# piston_stm.net
KiCad netlist of a schematic drawn in EAGLE
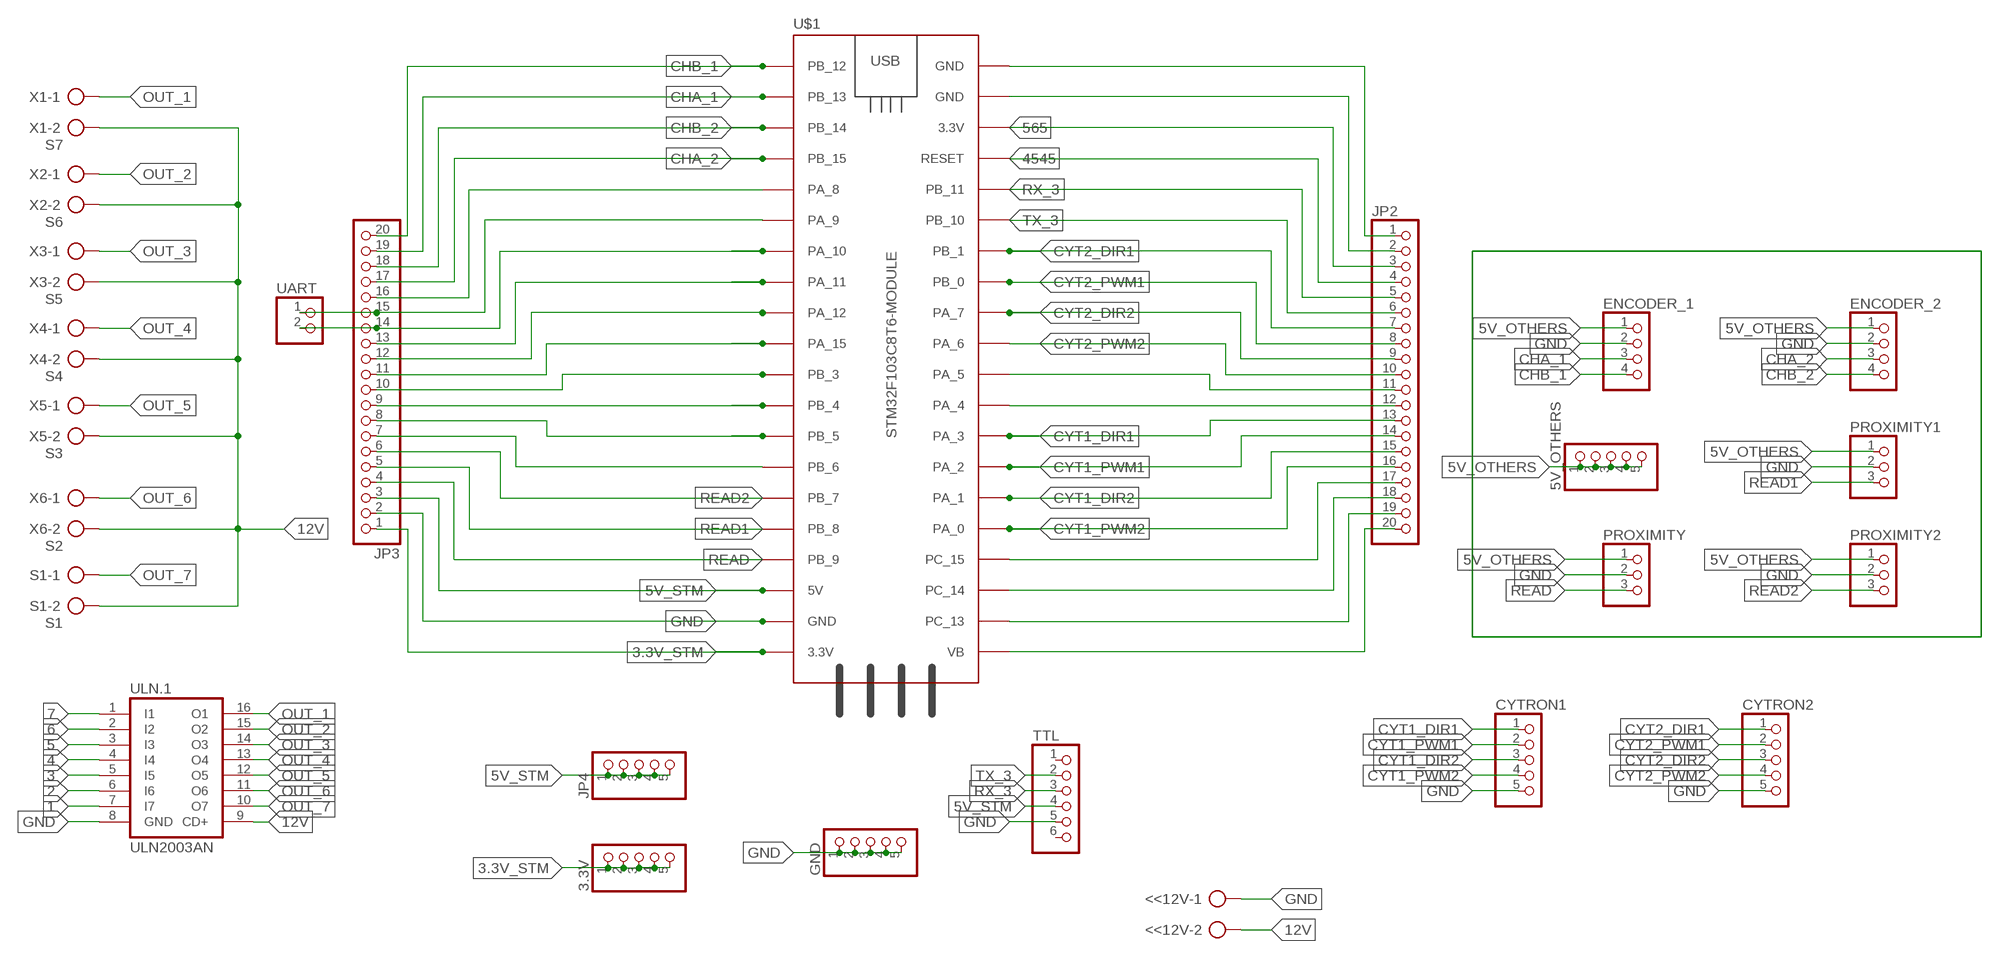
[diagram p0: schematic, sheet 1]

(export (version "E")
  (design (tool "Eeschema 10.0.6"))
  (components
    (comp (ref "3.3V")
      (value "PINHD-1X5")
      (footprint "eagle-import:1X05")
      (libsource (lib "eagle-import") (part "PINHD-1X5"))
    )
    (comp (ref "5V_OTHERS")
      (value "PINHD-1X5")
      (footprint "eagle-import:1X05")
      (libsource (lib "eagle-import") (part "PINHD-1X5"))
    )
    (comp (ref "<<12V")
      (value "AK300/2")
      (footprint "eagle-import:AK300_2")
      (libsource (lib "eagle-import") (part "AK300/2"))
    )
    (comp (ref "CYTRON1")
      (value "PINHD-5_DATA")
      (footprint "eagle-import:DATA_5")
      (libsource (lib "eagle-import") (part "PINHD-5_DATA"))
    )
    (comp (ref "CYTRON2")
      (value "PINHD-5_DATA")
      (footprint "eagle-import:DATA_5")
      (libsource (lib "eagle-import") (part "PINHD-5_DATA"))
    )
    (comp (ref "ENCODER_1")
      (value "PINHD-4_DATA")
      (footprint "eagle-import:DATA_4")
      (libsource (lib "eagle-import") (part "PINHD-4_DATA"))
    )
    (comp (ref "ENCODER_2")
      (value "PINHD-4_DATA")
      (footprint "eagle-import:DATA_4")
      (libsource (lib "eagle-import") (part "PINHD-4_DATA"))
    )
    (comp (ref "GND")
      (value "PINHD-1X5")
      (footprint "eagle-import:1X05")
      (libsource (lib "eagle-import") (part "PINHD-1X5"))
    )
    (comp (ref "JP2")
      (value "PINHD-1X20")
      (footprint "eagle-import:1X20")
      (libsource (lib "eagle-import") (part "PINHD-1X20"))
    )
    (comp (ref "JP3")
      (value "PINHD-1X20")
      (footprint "eagle-import:1X20")
      (libsource (lib "eagle-import") (part "PINHD-1X20"))
    )
    (comp (ref "JP4")
      (value "PINHD-1X5")
      (footprint "eagle-import:1X05")
      (libsource (lib "eagle-import") (part "PINHD-1X5"))
    )
    (comp (ref "PROXIMITY")
      (value "PINHD-3_DATA")
      (footprint "eagle-import:DATA_3")
      (libsource (lib "eagle-import") (part "PINHD-3_DATA"))
    )
    (comp (ref "PROXIMITY1")
      (value "PINHD-3_DATA")
      (footprint "eagle-import:DATA_3")
      (libsource (lib "eagle-import") (part "PINHD-3_DATA"))
    )
    (comp (ref "PROXIMITY2")
      (value "PINHD-3_DATA")
      (footprint "eagle-import:DATA_3")
      (libsource (lib "eagle-import") (part "PINHD-3_DATA"))
    )
    (comp (ref "S1")
      (value "S1")
      (footprint "eagle-import:AK300_2")
      (libsource (lib "eagle-import") (part "AK300/2"))
    )
    (comp (ref "TTL")
      (value "PINHD-6_DATA")
      (footprint "eagle-import:DATA_6")
      (libsource (lib "eagle-import") (part "PINHD-6_DATA"))
    )
    (comp (ref "U$1")
      (value "STM32F103C8T6-MODULE")
      (footprint "eagle-import:STM32F103C8T6-MODULE")
      (libsource (lib "eagle-import") (part "STM32F103C8T6-MODULE"))
    )
    (comp (ref "UART")
      (value "PINHD-2_DATA")
      (footprint "eagle-import:DATA_2")
      (libsource (lib "eagle-import") (part "PINHD-2_DATA"))
    )
    (comp (ref "ULN.1")
      (value "ULN2003AN")
      (footprint "eagle-import:DIL16")
      (libsource (lib "eagle-import") (part "ULN2003AN"))
    )
    (comp (ref "X1")
      (value "S7")
      (footprint "eagle-import:AK300_2")
      (libsource (lib "eagle-import") (part "AK300/2"))
    )
    (comp (ref "X2")
      (value "S6")
      (footprint "eagle-import:AK300_2")
      (libsource (lib "eagle-import") (part "AK300/2"))
    )
    (comp (ref "X3")
      (value "S5")
      (footprint "eagle-import:AK300_2")
      (libsource (lib "eagle-import") (part "AK300/2"))
    )
    (comp (ref "X4")
      (value "S4")
      (footprint "eagle-import:AK300_2")
      (libsource (lib "eagle-import") (part "AK300/2"))
    )
    (comp (ref "X5")
      (value "S3")
      (footprint "eagle-import:AK300_2")
      (libsource (lib "eagle-import") (part "AK300/2"))
    )
    (comp (ref "X6")
      (value "S2")
      (footprint "eagle-import:AK300_2")
      (libsource (lib "eagle-import") (part "AK300/2"))
    )
  )
  (nets
    (net (code "1") (name "1") (class "Default")
      (node (ref "JP3") (pin "13") (pinfunction "13_13") (pintype "passive"))
      (node (ref "U$1") (pin "PA_11") (pinfunction "PA_11_PA_11") (pintype "bidirectional"))
      (node (ref "ULN.1") (pin "7") (pinfunction "I7_7") (pintype "input"))
    )
    (net (code "2") (name "2") (class "Default")
      (node (ref "JP3") (pin "12") (pinfunction "12_12") (pintype "passive"))
      (node (ref "U$1") (pin "PA_12") (pinfunction "PA_12_PA_12") (pintype "bidirectional"))
      (node (ref "ULN.1") (pin "6") (pinfunction "I6_6") (pintype "input"))
    )
    (net (code "3") (name "3") (class "Default")
      (node (ref "JP3") (pin "11") (pinfunction "11_11") (pintype "passive"))
      (node (ref "U$1") (pin "PA_15") (pinfunction "PA_15_PA_15") (pintype "bidirectional"))
      (node (ref "ULN.1") (pin "5") (pinfunction "I5_5") (pintype "input"))
    )
    (net (code "4") (name "3.3V_STM") (class "Default")
      (node (ref "3.3V") (pin "1") (pinfunction "1_1") (pintype "passive"))
      (node (ref "3.3V") (pin "2") (pinfunction "2_2") (pintype "passive"))
      (node (ref "3.3V") (pin "3") (pinfunction "3_3") (pintype "passive"))
      (node (ref "3.3V") (pin "4") (pinfunction "4_4") (pintype "passive"))
      (node (ref "3.3V") (pin "5") (pinfunction "5_5") (pintype "passive"))
      (node (ref "JP3") (pin "1") (pinfunction "1_1") (pintype "passive"))
      (node (ref "U$1") (pin "3.3V_1") (pinfunction "3.3V_3.3V_1") (pintype "bidirectional"))
    )
    (net (code "5") (name "4") (class "Default")
      (node (ref "JP3") (pin "10") (pinfunction "10_10") (pintype "passive"))
      (node (ref "U$1") (pin "PB_3") (pinfunction "PB_3_PB_3") (pintype "bidirectional"))
      (node (ref "ULN.1") (pin "4") (pinfunction "I4_4") (pintype "input"))
    )
    (net (code "6") (name "5") (class "Default")
      (node (ref "JP3") (pin "9") (pinfunction "9_9") (pintype "passive"))
      (node (ref "U$1") (pin "PB_4") (pinfunction "PB_4_PB_4") (pintype "bidirectional"))
      (node (ref "ULN.1") (pin "3") (pinfunction "I3_3") (pintype "input"))
    )
    (net (code "7") (name "5V_OTHERS") (class "Default")
      (node (ref "5V_OTHERS") (pin "1") (pinfunction "1_1") (pintype "passive"))
      (node (ref "5V_OTHERS") (pin "2") (pinfunction "2_2") (pintype "passive"))
      (node (ref "5V_OTHERS") (pin "3") (pinfunction "3_3") (pintype "passive"))
      (node (ref "5V_OTHERS") (pin "4") (pinfunction "4_4") (pintype "passive"))
      (node (ref "5V_OTHERS") (pin "5") (pinfunction "5_5") (pintype "passive"))
      (node (ref "ENCODER_1") (pin "1") (pinfunction "1_1") (pintype "passive"))
      (node (ref "ENCODER_2") (pin "1") (pinfunction "1_1") (pintype "passive"))
      (node (ref "PROXIMITY") (pin "1") (pinfunction "1_1") (pintype "passive"))
      (node (ref "PROXIMITY1") (pin "1") (pinfunction "1_1") (pintype "passive"))
      (node (ref "PROXIMITY2") (pin "1") (pinfunction "1_1") (pintype "passive"))
    )
    (net (code "8") (name "5V_STM") (class "Default")
      (node (ref "JP3") (pin "3") (pinfunction "3_3") (pintype "passive"))
      (node (ref "JP4") (pin "1") (pinfunction "1_1") (pintype "passive"))
      (node (ref "JP4") (pin "2") (pinfunction "2_2") (pintype "passive"))
      (node (ref "JP4") (pin "3") (pinfunction "3_3") (pintype "passive"))
      (node (ref "JP4") (pin "4") (pinfunction "4_4") (pintype "passive"))
      (node (ref "JP4") (pin "5") (pinfunction "5_5") (pintype "passive"))
      (node (ref "TTL") (pin "4") (pinfunction "4_4") (pintype "passive"))
      (node (ref "U$1") (pin "5V") (pinfunction "5V_5V") (pintype "bidirectional"))
    )
    (net (code "9") (name "6") (class "Default")
      (node (ref "JP3") (pin "8") (pinfunction "8_8") (pintype "passive"))
      (node (ref "U$1") (pin "PB_5") (pinfunction "PB_5_PB_5") (pintype "bidirectional"))
      (node (ref "ULN.1") (pin "2") (pinfunction "I2_2") (pintype "input"))
    )
    (net (code "10") (name "7") (class "Default")
      (node (ref "JP2") (pin "12") (pinfunction "12_12") (pintype "passive"))
      (node (ref "U$1") (pin "PA_4") (pinfunction "PA_4_PA_4") (pintype "bidirectional"))
      (node (ref "ULN.1") (pin "1") (pinfunction "I1_1") (pintype "input"))
    )
    (net (code "11") (name "12V") (class "Default")
      (node (ref "<<12V") (pin "2") (pinfunction "KL_2") (pintype "passive"))
      (node (ref "S1") (pin "2") (pinfunction "KL_2") (pintype "passive"))
      (node (ref "ULN.1") (pin "9") (pinfunction "CD+_9") (pintype "passive"))
      (node (ref "X1") (pin "2") (pinfunction "KL_2") (pintype "passive"))
      (node (ref "X2") (pin "2") (pinfunction "KL_2") (pintype "passive"))
      (node (ref "X3") (pin "2") (pinfunction "KL_2") (pintype "passive"))
      (node (ref "X4") (pin "2") (pinfunction "KL_2") (pintype "passive"))
      (node (ref "X5") (pin "2") (pinfunction "KL_2") (pintype "passive"))
      (node (ref "X6") (pin "2") (pinfunction "KL_2") (pintype "passive"))
    )
    (net (code "12") (name "565") (class "Default")
      (node (ref "JP2") (pin "3") (pinfunction "3_3") (pintype "passive"))
      (node (ref "U$1") (pin "3.3V_2") (pinfunction "3.3V_3.3V_2") (pintype "bidirectional"))
    )
    (net (code "13") (name "4545") (class "Default")
      (node (ref "JP2") (pin "4") (pinfunction "4_4") (pintype "passive"))
      (node (ref "U$1") (pin "RESET") (pinfunction "RESET_RESET") (pintype "bidirectional"))
    )
    (net (code "14") (name "CHA_1") (class "Default")
      (node (ref "ENCODER_1") (pin "3") (pinfunction "3_3") (pintype "passive"))
      (node (ref "JP3") (pin "19") (pinfunction "19_19") (pintype "passive"))
      (node (ref "U$1") (pin "PB_13") (pinfunction "PB_13_PB_13") (pintype "bidirectional"))
    )
    (net (code "15") (name "CHA_2") (class "Default")
      (node (ref "ENCODER_2") (pin "3") (pinfunction "3_3") (pintype "passive"))
      (node (ref "JP3") (pin "17") (pinfunction "17_17") (pintype "passive"))
      (node (ref "U$1") (pin "PB_15") (pinfunction "PB_15_PB_15") (pintype "bidirectional"))
    )
    (net (code "16") (name "CHB_1") (class "Default")
      (node (ref "ENCODER_1") (pin "4") (pinfunction "4_4") (pintype "passive"))
      (node (ref "JP3") (pin "20") (pinfunction "20_20") (pintype "passive"))
      (node (ref "U$1") (pin "PB_12") (pinfunction "PB_12_PB_12") (pintype "bidirectional"))
    )
    (net (code "17") (name "CHB_2") (class "Default")
      (node (ref "ENCODER_2") (pin "4") (pinfunction "4_4") (pintype "passive"))
      (node (ref "JP3") (pin "18") (pinfunction "18_18") (pintype "passive"))
      (node (ref "U$1") (pin "PB_14") (pinfunction "PB_14_PB_14") (pintype "bidirectional"))
    )
    (net (code "18") (name "CYT1_DIR1") (class "Default")
      (node (ref "CYTRON1") (pin "1") (pinfunction "1_1") (pintype "passive"))
      (node (ref "JP2") (pin "13") (pinfunction "13_13") (pintype "passive"))
      (node (ref "U$1") (pin "PA_3") (pinfunction "PA_3_PA_3") (pintype "bidirectional"))
    )
    (net (code "19") (name "CYT1_DIR2") (class "Default")
      (node (ref "CYTRON1") (pin "3") (pinfunction "3_3") (pintype "passive"))
      (node (ref "JP2") (pin "15") (pinfunction "15_15") (pintype "passive"))
      (node (ref "U$1") (pin "PA_1") (pinfunction "PA_1_PA_1") (pintype "bidirectional"))
    )
    (net (code "20") (name "CYT1_PWM1") (class "Default")
      (node (ref "CYTRON1") (pin "2") (pinfunction "2_2") (pintype "passive"))
      (node (ref "JP2") (pin "14") (pinfunction "14_14") (pintype "passive"))
      (node (ref "U$1") (pin "PA_2") (pinfunction "PA_2_PA_2") (pintype "bidirectional"))
    )
    (net (code "21") (name "CYT1_PWM2") (class "Default")
      (node (ref "CYTRON1") (pin "4") (pinfunction "4_4") (pintype "passive"))
      (node (ref "JP2") (pin "16") (pinfunction "16_16") (pintype "passive"))
      (node (ref "U$1") (pin "PA_0") (pinfunction "PA_0_PA_0") (pintype "bidirectional"))
    )
    (net (code "22") (name "CYT2_DIR1") (class "Default")
      (node (ref "CYTRON2") (pin "1") (pinfunction "1_1") (pintype "passive"))
      (node (ref "JP2") (pin "7") (pinfunction "7_7") (pintype "passive"))
      (node (ref "U$1") (pin "PB_1") (pinfunction "PB_1_PB_1") (pintype "bidirectional"))
    )
    (net (code "23") (name "CYT2_DIR2") (class "Default")
      (node (ref "CYTRON2") (pin "3") (pinfunction "3_3") (pintype "passive"))
      (node (ref "JP2") (pin "9") (pinfunction "9_9") (pintype "passive"))
      (node (ref "U$1") (pin "PA_7") (pinfunction "PA_7_PA_7") (pintype "bidirectional"))
    )
    (net (code "24") (name "CYT2_PWM1") (class "Default")
      (node (ref "CYTRON2") (pin "2") (pinfunction "2_2") (pintype "passive"))
      (node (ref "JP2") (pin "8") (pinfunction "8_8") (pintype "passive"))
      (node (ref "U$1") (pin "PB_0") (pinfunction "PB_0_PB_0") (pintype "bidirectional"))
    )
    (net (code "25") (name "CYT2_PWM2") (class "Default")
      (node (ref "CYTRON2") (pin "4") (pinfunction "4_4") (pintype "passive"))
      (node (ref "JP2") (pin "10") (pinfunction "10_10") (pintype "passive"))
      (node (ref "U$1") (pin "PA_6") (pinfunction "PA_6_PA_6") (pintype "bidirectional"))
    )
    (net (code "26") (name "GND") (class "Default")
      (node (ref "<<12V") (pin "1") (pinfunction "KL_1") (pintype "passive"))
      (node (ref "CYTRON1") (pin "5") (pinfunction "5_5") (pintype "passive"))
      (node (ref "CYTRON2") (pin "5") (pinfunction "5_5") (pintype "passive"))
      (node (ref "ENCODER_1") (pin "2") (pinfunction "2_2") (pintype "passive"))
      (node (ref "ENCODER_2") (pin "2") (pinfunction "2_2") (pintype "passive"))
      (node (ref "GND") (pin "1") (pinfunction "1_1") (pintype "passive"))
      (node (ref "GND") (pin "2") (pinfunction "2_2") (pintype "passive"))
      (node (ref "GND") (pin "3") (pinfunction "3_3") (pintype "passive"))
      (node (ref "GND") (pin "4") (pinfunction "4_4") (pintype "passive"))
      (node (ref "GND") (pin "5") (pinfunction "5_5") (pintype "passive"))
      (node (ref "JP2") (pin "1") (pinfunction "1_1") (pintype "passive"))
      (node (ref "JP2") (pin "2") (pinfunction "2_2") (pintype "passive"))
      (node (ref "JP3") (pin "2") (pinfunction "2_2") (pintype "passive"))
      (node (ref "PROXIMITY") (pin "2") (pinfunction "2_2") (pintype "passive"))
      (node (ref "PROXIMITY1") (pin "2") (pinfunction "2_2") (pintype "passive"))
      (node (ref "PROXIMITY2") (pin "2") (pinfunction "2_2") (pintype "passive"))
      (node (ref "TTL") (pin "5") (pinfunction "5_5") (pintype "passive"))
      (node (ref "U$1") (pin "GND_1") (pinfunction "GND_GND_1") (pintype "bidirectional"))
      (node (ref "U$1") (pin "GND_2") (pinfunction "GND_GND_2") (pintype "bidirectional"))
      (node (ref "U$1") (pin "GND_3") (pinfunction "GND_GND_3") (pintype "power_in"))
      (node (ref "ULN.1") (pin "8") (pinfunction "GND_8") (pintype "power_in"))
    )
    (net (code "27") (name "Net-(JP2-Pad11)") (class "Default")
      (node (ref "JP2") (pin "11") (pinfunction "11_11") (pintype "passive"))
      (node (ref "U$1") (pin "PA_5") (pinfunction "PA_5_PA_5") (pintype "bidirectional"))
    )
    (net (code "28") (name "Net-(JP2-Pad17)") (class "Default")
      (node (ref "JP2") (pin "17") (pinfunction "17_17") (pintype "passive"))
      (node (ref "U$1") (pin "PC_15") (pinfunction "PC_15_PC_15") (pintype "bidirectional"))
    )
    (net (code "29") (name "Net-(JP2-Pad18)") (class "Default")
      (node (ref "JP2") (pin "18") (pinfunction "18_18") (pintype "passive"))
      (node (ref "U$1") (pin "PC_14") (pinfunction "PC_14_PC_14") (pintype "bidirectional"))
    )
    (net (code "30") (name "Net-(JP2-Pad19)") (class "Default")
      (node (ref "JP2") (pin "19") (pinfunction "19_19") (pintype "passive"))
      (node (ref "U$1") (pin "PC_13") (pinfunction "PC_13_PC_13") (pintype "bidirectional"))
    )
    (net (code "31") (name "Net-(JP2-Pad20)") (class "Default")
      (node (ref "JP2") (pin "20") (pinfunction "20_20") (pintype "passive"))
      (node (ref "U$1") (pin "VB") (pinfunction "VB_VB") (pintype "bidirectional"))
    )
    (net (code "32") (name "Net-(JP3-Pad7)") (class "Default")
      (node (ref "JP3") (pin "7") (pinfunction "7_7") (pintype "passive"))
      (node (ref "U$1") (pin "PB_6") (pinfunction "PB_6_PB_6") (pintype "bidirectional"))
    )
    (net (code "33") (name "Net-(JP3-Pad14)") (class "Default")
      (node (ref "JP3") (pin "14") (pinfunction "14_14") (pintype "passive"))
      (node (ref "U$1") (pin "PA_10") (pinfunction "PA_10_PA_10") (pintype "bidirectional"))
      (node (ref "UART") (pin "2") (pinfunction "2_2") (pintype "passive"))
    )
    (net (code "34") (name "Net-(JP3-Pad15)") (class "Default")
      (node (ref "JP3") (pin "15") (pinfunction "15_15") (pintype "passive"))
      (node (ref "U$1") (pin "PA_9") (pinfunction "PA_9_PA_9") (pintype "bidirectional"))
      (node (ref "UART") (pin "1") (pinfunction "1_1") (pintype "passive"))
    )
    (net (code "35") (name "Net-(JP3-Pad16)") (class "Default")
      (node (ref "JP3") (pin "16") (pinfunction "16_16") (pintype "passive"))
      (node (ref "U$1") (pin "PA_8") (pinfunction "PA_8_PA_8") (pintype "bidirectional"))
    )
    (net (code "36") (name "OUT_1") (class "Default")
      (node (ref "ULN.1") (pin "16") (pinfunction "O1_16") (pintype "open_collector"))
      (node (ref "X1") (pin "1") (pinfunction "KL_1") (pintype "passive"))
    )
    (net (code "37") (name "OUT_2") (class "Default")
      (node (ref "ULN.1") (pin "15") (pinfunction "O2_15") (pintype "open_collector"))
      (node (ref "X2") (pin "1") (pinfunction "KL_1") (pintype "passive"))
    )
    (net (code "38") (name "OUT_3") (class "Default")
      (node (ref "ULN.1") (pin "14") (pinfunction "O3_14") (pintype "open_collector"))
      (node (ref "X3") (pin "1") (pinfunction "KL_1") (pintype "passive"))
    )
    (net (code "39") (name "OUT_4") (class "Default")
      (node (ref "ULN.1") (pin "13") (pinfunction "O4_13") (pintype "open_collector"))
      (node (ref "X4") (pin "1") (pinfunction "KL_1") (pintype "passive"))
    )
    (net (code "40") (name "OUT_5") (class "Default")
      (node (ref "ULN.1") (pin "12") (pinfunction "O5_12") (pintype "open_collector"))
      (node (ref "X5") (pin "1") (pinfunction "KL_1") (pintype "passive"))
    )
    (net (code "41") (name "OUT_6") (class "Default")
      (node (ref "ULN.1") (pin "11") (pinfunction "O6_11") (pintype "open_collector"))
      (node (ref "X6") (pin "1") (pinfunction "KL_1") (pintype "passive"))
    )
    (net (code "42") (name "OUT_7") (class "Default")
      (node (ref "S1") (pin "1") (pinfunction "KL_1") (pintype "passive"))
      (node (ref "ULN.1") (pin "10") (pinfunction "O7_10") (pintype "open_collector"))
    )
    (net (code "43") (name "READ") (class "Default")
      (node (ref "JP3") (pin "4") (pinfunction "4_4") (pintype "passive"))
      (node (ref "PROXIMITY") (pin "3") (pinfunction "3_3") (pintype "passive"))
      (node (ref "U$1") (pin "PB_9") (pinfunction "PB_9_PB_9") (pintype "bidirectional"))
    )
    (net (code "44") (name "READ1") (class "Default")
      (node (ref "JP3") (pin "5") (pinfunction "5_5") (pintype "passive"))
      (node (ref "PROXIMITY1") (pin "3") (pinfunction "3_3") (pintype "passive"))
      (node (ref "U$1") (pin "PB_8") (pinfunction "PB_8_PB_8") (pintype "bidirectional"))
    )
    (net (code "45") (name "READ2") (class "Default")
      (node (ref "JP3") (pin "6") (pinfunction "6_6") (pintype "passive"))
      (node (ref "PROXIMITY2") (pin "3") (pinfunction "3_3") (pintype "passive"))
      (node (ref "U$1") (pin "PB_7") (pinfunction "PB_7_PB_7") (pintype "bidirectional"))
    )
    (net (code "46") (name "RX_3") (class "Default")
      (node (ref "JP2") (pin "5") (pinfunction "5_5") (pintype "passive"))
      (node (ref "TTL") (pin "3") (pinfunction "3_3") (pintype "passive"))
      (node (ref "U$1") (pin "PB_11") (pinfunction "PB_11_PB_11") (pintype "bidirectional"))
    )
    (net (code "47") (name "TX_3") (class "Default")
      (node (ref "JP2") (pin "6") (pinfunction "6_6") (pintype "passive"))
      (node (ref "TTL") (pin "2") (pinfunction "2_2") (pintype "passive"))
      (node (ref "U$1") (pin "PB_10") (pinfunction "PB_10_PB_10") (pintype "bidirectional"))
    )
    (net (code "48") (name "unconnected-(TTL-Pad1)") (class "Default")
      (node (ref "TTL") (pin "1") (pinfunction "1_1") (pintype "passive"))
    )
    (net (code "49") (name "unconnected-(TTL-Pad6)") (class "Default")
      (node (ref "TTL") (pin "6") (pinfunction "6_6") (pintype "passive"))
    )
  )
)
